# rc_1.net
KiCad netlist of a schematic drawn in EAGLE
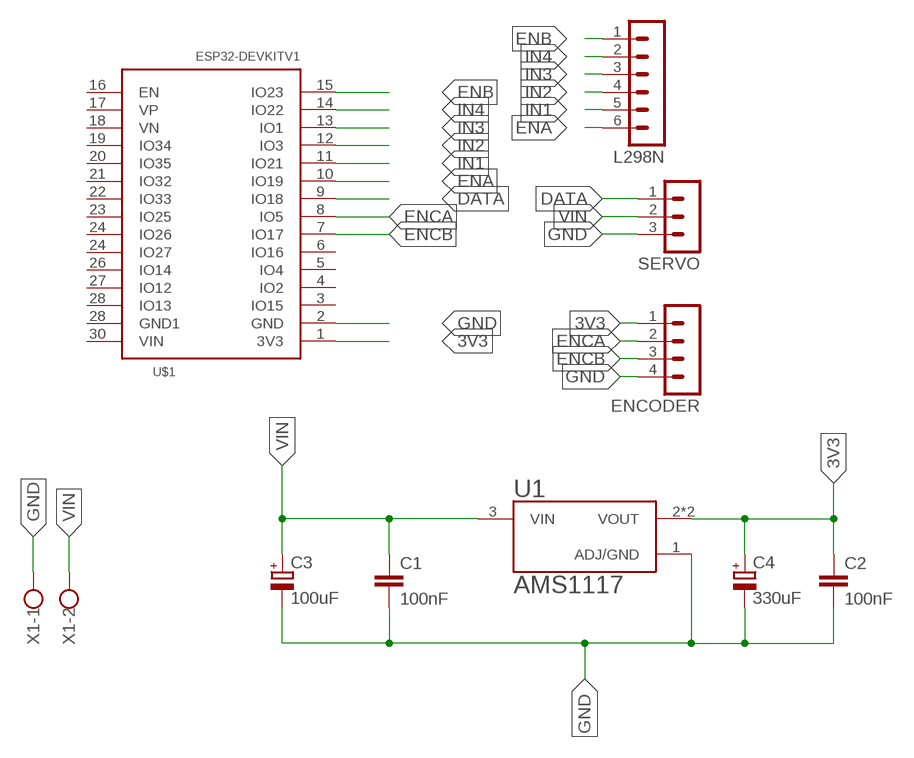
[diagram p0: schematic, sheet 1]

(export (version "E")
  (design (tool "Eeschema 10.0.6"))
  (components
    (comp (ref "C1")
      (value "100nF")
      (footprint "eagle-import:C0805")
      (libsource (lib "eagle-import") (part "C-EUC0805"))
    )
    (comp (ref "C2")
      (value "100nF")
      (footprint "eagle-import:C0805")
      (libsource (lib "eagle-import") (part "C-EUC0805"))
    )
    (comp (ref "C3")
      (value "100uF")
      (footprint "eagle-import:CT6032")
      (libsource (lib "eagle-import") (part "CPOL-EUCT6032"))
    )
    (comp (ref "C4")
      (value "330uF")
      (footprint "eagle-import:CT6032")
      (libsource (lib "eagle-import") (part "CPOL-EUCT6032"))
    )
    (comp (ref "ENCODER")
      (value "MA04-1")
      (footprint "eagle-import:MA04-1")
      (libsource (lib "eagle-import") (part "MA04-1"))
    )
    (comp (ref "L298N")
      (value "MA06-1")
      (footprint "eagle-import:MA06-1")
      (libsource (lib "eagle-import") (part "MA06-1"))
    )
    (comp (ref "SERVO")
      (value "MA03-1")
      (footprint "eagle-import:MA03-1")
      (libsource (lib "eagle-import") (part "MA03-1"))
    )
    (comp (ref "U$1")
      (value "ESP32DEVKITV1")
      (footprint "eagle-import:ESP32-DEVKITV1")
      (libsource (lib "eagle-import") (part "ESP32DEVKITV1"))
    )
    (comp (ref "U1")
      (value "AMS1117")
      (footprint "eagle-import:SOT229P700X180-4N")
      (fields (field (name "MF") "Advanced Monolithic Systems"))
      (libsource (lib "eagle-import") (part "AMS1117"))
    )
    (comp (ref "X1")
      (value "W237-102")
      (footprint "eagle-import:W237-102")
      (fields (field (name "MPN") "237-102"))
      (libsource (lib "eagle-import") (part "W237-102"))
    )
  )
  (nets
    (net (code "1") (name "3V3") (class "Default")
      (node (ref "C2") (pin "1") (pinfunction "1_1") (pintype "passive"))
      (node (ref "C4") (pin "+") (pinfunction "+_+") (pintype "passive"))
      (node (ref "ENCODER") (pin "1") (pinfunction "1_1") (pintype "passive"))
      (node (ref "U$1") (pin "1") (pinfunction "3V3_1") (pintype "bidirectional"))
      (node (ref "U1") (pin "2") (pinfunction "VOUT_2") (pintype "output"))
      (node (ref "U1") (pin "4") (pinfunction "VOUT_4") (pintype "output"))
    )
    (net (code "2") (name "DATA") (class "Default")
      (node (ref "SERVO") (pin "1") (pinfunction "1_1") (pintype "passive"))
      (node (ref "U$1") (pin "9") (pinfunction "IO18_9") (pintype "bidirectional"))
    )
    (net (code "3") (name "ENA") (class "Default")
      (node (ref "L298N") (pin "6") (pinfunction "6_6") (pintype "passive"))
      (node (ref "U$1") (pin "10") (pinfunction "IO19_10") (pintype "bidirectional"))
    )
    (net (code "4") (name "ENB") (class "Default")
      (node (ref "L298N") (pin "1") (pinfunction "1_1") (pintype "passive"))
      (node (ref "U$1") (pin "15") (pinfunction "IO23_15") (pintype "bidirectional"))
    )
    (net (code "5") (name "ENCA") (class "Default")
      (node (ref "ENCODER") (pin "2") (pinfunction "2_2") (pintype "passive"))
      (node (ref "U$1") (pin "8") (pinfunction "IO5_8") (pintype "bidirectional"))
    )
    (net (code "6") (name "ENCB") (class "Default")
      (node (ref "ENCODER") (pin "3") (pinfunction "3_3") (pintype "passive"))
      (node (ref "U$1") (pin "7") (pinfunction "IO17_7") (pintype "bidirectional"))
    )
    (net (code "7") (name "GND") (class "Default")
      (node (ref "C1") (pin "2") (pinfunction "2_2") (pintype "passive"))
      (node (ref "C2") (pin "2") (pinfunction "2_2") (pintype "passive"))
      (node (ref "C3") (pin "-") (pinfunction "-_-") (pintype "passive"))
      (node (ref "C4") (pin "-") (pinfunction "-_-") (pintype "passive"))
      (node (ref "ENCODER") (pin "4") (pinfunction "4_4") (pintype "passive"))
      (node (ref "SERVO") (pin "3") (pinfunction "3_3") (pintype "passive"))
      (node (ref "U$1") (pin "2") (pinfunction "GND_2") (pintype "bidirectional"))
      (node (ref "U1") (pin "1") (pinfunction "ADJ/GND_1") (pintype "power_in"))
      (node (ref "X1") (pin "1") (pinfunction "KL_1") (pintype "passive"))
    )
    (net (code "8") (name "IN1") (class "Default")
      (node (ref "L298N") (pin "5") (pinfunction "5_5") (pintype "passive"))
      (node (ref "U$1") (pin "11") (pinfunction "IO21_11") (pintype "bidirectional"))
    )
    (net (code "9") (name "IN2") (class "Default")
      (node (ref "L298N") (pin "4") (pinfunction "4_4") (pintype "passive"))
      (node (ref "U$1") (pin "12") (pinfunction "IO3_12") (pintype "bidirectional"))
    )
    (net (code "10") (name "IN3") (class "Default")
      (node (ref "L298N") (pin "3") (pinfunction "3_3") (pintype "passive"))
      (node (ref "U$1") (pin "13") (pinfunction "IO1_13") (pintype "bidirectional"))
    )
    (net (code "11") (name "IN4") (class "Default")
      (node (ref "L298N") (pin "2") (pinfunction "2_2") (pintype "passive"))
      (node (ref "U$1") (pin "14") (pinfunction "IO22_14") (pintype "bidirectional"))
    )
    (net (code "12") (name "VIN") (class "Default")
      (node (ref "C1") (pin "1") (pinfunction "1_1") (pintype "passive"))
      (node (ref "C3") (pin "+") (pinfunction "+_+") (pintype "passive"))
      (node (ref "SERVO") (pin "2") (pinfunction "2_2") (pintype "passive"))
      (node (ref "U1") (pin "3") (pinfunction "VIN_3") (pintype "input"))
      (node (ref "X1") (pin "2") (pinfunction "KL_2") (pintype "passive"))
    )
    (net (code "13") (name "unconnected-(U$1-EN-Pad16)") (class "Default")
      (node (ref "U$1") (pin "16") (pinfunction "EN_16") (pintype "bidirectional"))
    )
    (net (code "14") (name "unconnected-(U$1-GND1-Pad28)") (class "Default")
      (node (ref "U$1") (pin "28") (pinfunction "GND1_28") (pintype "bidirectional"))
    )
    (net (code "15") (name "unconnected-(U$1-IO2-Pad4)") (class "Default")
      (node (ref "U$1") (pin "4") (pinfunction "IO2_4") (pintype "bidirectional"))
    )
    (net (code "16") (name "unconnected-(U$1-IO4-Pad5)") (class "Default")
      (node (ref "U$1") (pin "5") (pinfunction "IO4_5") (pintype "bidirectional"))
    )
    (net (code "17") (name "unconnected-(U$1-IO12-Pad27)") (class "Default")
      (node (ref "U$1") (pin "27") (pinfunction "IO12_27") (pintype "bidirectional"))
    )
    (net (code "18") (name "unconnected-(U$1-IO13-Pad28)") (class "Default")
      (node (ref "U$1") (pin "28") (pinfunction "IO13_28") (pintype "bidirectional"))
    )
    (net (code "19") (name "unconnected-(U$1-IO14-Pad26)") (class "Default")
      (node (ref "U$1") (pin "26") (pinfunction "IO14_26") (pintype "bidirectional"))
    )
    (net (code "20") (name "unconnected-(U$1-IO15-Pad3)") (class "Default")
      (node (ref "U$1") (pin "3") (pinfunction "IO15_3") (pintype "bidirectional"))
    )
    (net (code "21") (name "unconnected-(U$1-IO16-Pad6)") (class "Default")
      (node (ref "U$1") (pin "6") (pinfunction "IO16_6") (pintype "bidirectional"))
    )
    (net (code "22") (name "unconnected-(U$1-IO25-Pad23)") (class "Default")
      (node (ref "U$1") (pin "23") (pinfunction "IO25_23") (pintype "bidirectional"))
    )
    (net (code "23") (name "unconnected-(U$1-IO26-Pad24)") (class "Default")
      (node (ref "U$1") (pin "24") (pinfunction "IO26_24") (pintype "bidirectional"))
    )
    (net (code "24") (name "unconnected-(U$1-IO27-Pad24)") (class "Default")
      (node (ref "U$1") (pin "24") (pinfunction "IO27_24") (pintype "bidirectional"))
    )
    (net (code "25") (name "unconnected-(U$1-IO32-Pad21)") (class "Default")
      (node (ref "U$1") (pin "21") (pinfunction "IO32_21") (pintype "bidirectional"))
    )
    (net (code "26") (name "unconnected-(U$1-IO33-Pad22)") (class "Default")
      (node (ref "U$1") (pin "22") (pinfunction "IO33_22") (pintype "bidirectional"))
    )
    (net (code "27") (name "unconnected-(U$1-IO34-Pad19)") (class "Default")
      (node (ref "U$1") (pin "19") (pinfunction "IO34_19") (pintype "bidirectional"))
    )
    (net (code "28") (name "unconnected-(U$1-IO35-Pad20)") (class "Default")
      (node (ref "U$1") (pin "20") (pinfunction "IO35_20") (pintype "bidirectional"))
    )
    (net (code "29") (name "unconnected-(U$1-VIN-Pad30)") (class "Default")
      (node (ref "U$1") (pin "30") (pinfunction "VIN_30") (pintype "bidirectional"))
    )
    (net (code "30") (name "unconnected-(U$1-VN-Pad18)") (class "Default")
      (node (ref "U$1") (pin "18") (pinfunction "VN_18") (pintype "bidirectional"))
    )
    (net (code "31") (name "unconnected-(U$1-VP-Pad17)") (class "Default")
      (node (ref "U$1") (pin "17") (pinfunction "VP_17") (pintype "bidirectional"))
    )
  )
)
